# 1-12.net
KiCad netlist of a schematic drawn in EasyEDA Pro
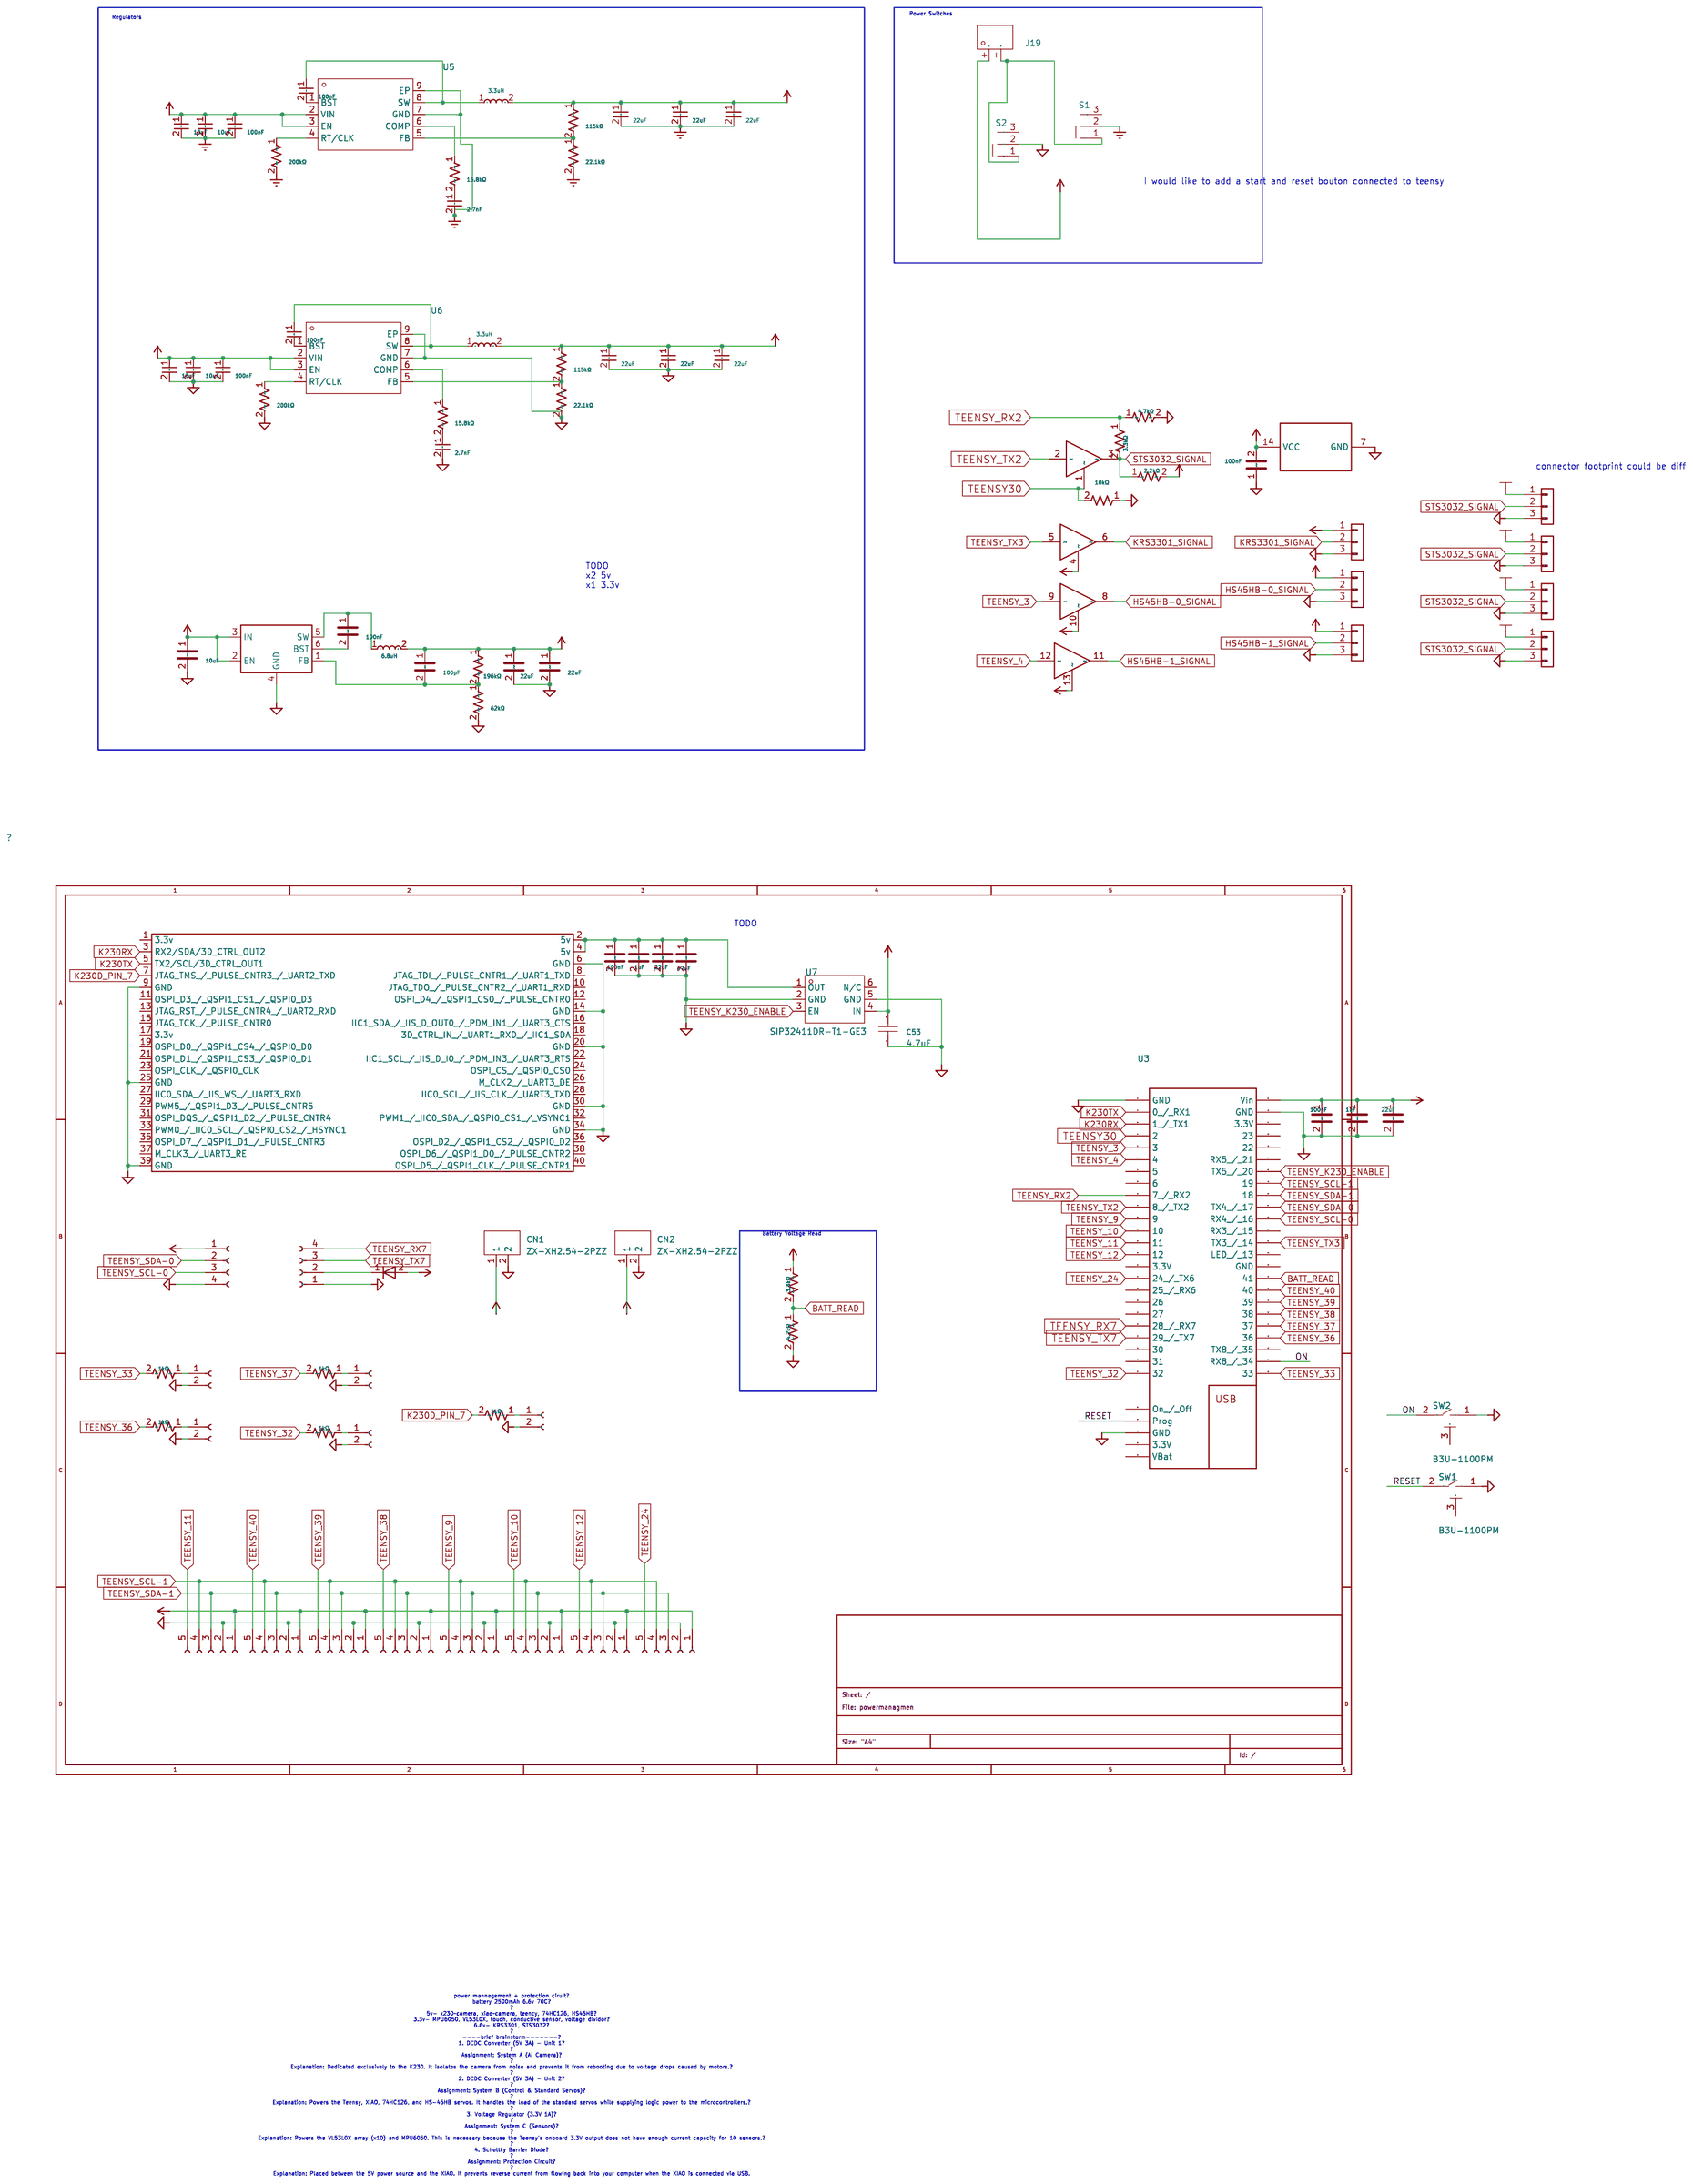
[diagram p0: schematic sheet]

(export (version "E")
  (design (tool "Eeschema 10.0.6"))
  (components
    (comp (ref "C1")
      (value "100nF")
      (description "Capacitance:100nF Tolerance:±10% Tolerance:±10% Voltage Rating:50V Temperature Coefficient:X7R")
      (fields
        (field (name "Manufacturer Part") "TCC0603X7R104K500CT")
        (field (name "Manufacturer") "CCTC(三环)")
      )
      (libsource (lib "easyedapro") (part "Device_C"))
    )
    (comp (ref "C2")
      (value "22uF")
      (description "Capacitance:22uF Tolerance:±20% Tolerance:±20% Voltage Rating:10V Temperature Coefficient:X5R")
      (fields
        (field (name "Manufacturer Part") "CL10A226MP8NUNE")
        (field (name "Manufacturer") "SAMSUNG(三星)")
      )
      (libsource (lib "easyedapro") (part "Device_C"))
    )
    (comp (ref "C3")
      (value "1uF")
      (description "Capacitance:1uF Tolerance:±10% Tolerance:±10% Voltage Rating:50V Temperature Coefficient:X5R")
      (fields
        (field (name "Manufacturer Part") "CL10A105KB8NNNC")
        (field (name "Manufacturer") "SAMSUNG(三星)")
      )
      (libsource (lib "easyedapro") (part "Device_C"))
    )
    (comp (ref "C4")
      (value "100nF")
      (description "Capacitance:100nF Tolerance:±10% Tolerance:±10% Voltage Rating:50V Temperature Coefficient:X7R")
      (fields
        (field (name "Manufacturer Part") "TCC0603X7R104K500CT")
        (field (name "Manufacturer") "CCTC(三环)")
      )
      (libsource (lib "easyedapro") (part "Device_C"))
    )
    (comp (ref "C5")
      (value "10uF")
      (description "Capacitance:10uF Tolerance:±20% Tolerance:±20% Voltage Rating:16V Temperature Coefficient:X5R")
      (fields
        (field (name "Manufacturer Part") "CL10A106MO8NQNC")
        (field (name "Manufacturer") "SAMSUNG(三星)")
      )
      (libsource (lib "easyedapro") (part "Device_C_Small"))
    )
    (comp (ref "C10")
      (value "100pF")
      (description "Capacitance:100pF Tolerance:±5% Tolerance:±5% Voltage Rating:50V Temperature Coefficient:C0G")
      (fields
        (field (name "Manufacturer Part") "CL10C101JB8NNNC")
        (field (name "Manufacturer") "SAMSUNG(三星)")
      )
      (libsource (lib "easyedapro") (part "Device_C"))
    )
    (comp (ref "C17")
      (value "100nF")
      (description "Capacitance:100nF Tolerance:±10% Tolerance:±10% Voltage Rating:50V Temperature Coefficient:X7R")
      (fields
        (field (name "Manufacturer Part") "TCC0603X7R104K500CT")
        (field (name "Manufacturer") "CCTC(三环)")
      )
      (libsource (lib "easyedapro") (part "Device_C"))
    )
    (comp (ref "C18")
      (value "1uF")
      (description "Capacitance:1uF Tolerance:±10% Tolerance:±10% Voltage Rating:50V Temperature Coefficient:X5R")
      (fields
        (field (name "Manufacturer Part") "CL10A105KB8NNNC")
        (field (name "Manufacturer") "SAMSUNG(三星)")
      )
      (libsource (lib "easyedapro") (part "Device_C"))
    )
    (comp (ref "C19")
      (value "22uF")
      (description "Capacitance:22uF Tolerance:±20% Tolerance:±20% Voltage Rating:10V Temperature Coefficient:X5R")
      (fields
        (field (name "Manufacturer Part") "CL10A226MP8NUNE")
        (field (name "Manufacturer") "SAMSUNG(三星)")
      )
      (libsource (lib "easyedapro") (part "Device_C"))
    )
    (comp (ref "C20")
      (value "47uF")
      (description "Capacitance:47uF Tolerance:±20% Tolerance:±20% Voltage Rating:6.3V Temperature Coefficient:X5R")
      (fields
        (field (name "Manufacturer Part") "GRM188R60J476ME15D")
        (field (name "Manufacturer") "muRata(村田)")
      )
      (libsource (lib "easyedapro") (part "Device_C"))
    )
    (comp (ref "C21")
      (value "22uF")
      (description "Capacitance:22uF Tolerance:±20% Tolerance:±20% Voltage Rating:10V Temperature Coefficient:X5R")
      (fields
        (field (name "Manufacturer Part") "CL10A226MP8NUNE")
        (field (name "Manufacturer") "SAMSUNG(三星)")
      )
      (libsource (lib "easyedapro") (part "Device_C"))
    )
    (comp (ref "C22")
      (value "10uF")
      (description "Capacitance:10uF Tolerance:±20% Tolerance:±20% Voltage Rating:16V Temperature Coefficient:X5R")
      (fields
        (field (name "Manufacturer Part") "CL10A106MO8NQNC")
        (field (name "Manufacturer") "SAMSUNG(三星)")
      )
      (libsource (lib "easyedapro") (part "Device_C_Small"))
    )
    (comp (ref "C23")
      (value "100nF")
      (description "Capacitance:100nF Tolerance:±10% Tolerance:±10% Voltage Rating:50V Temperature Coefficient:X7R")
      (fields
        (field (name "Manufacturer Part") "TCC0603X7R104K500CT")
        (field (name "Manufacturer") "CCTC(三环)")
      )
      (libsource (lib "easyedapro") (part "Device_C"))
    )
    (comp (ref "C24")
      (value "100nF")
      (description "Capacitance:100nF Tolerance:±10% Tolerance:±10% Voltage Rating:50V Temperature Coefficient:X7R")
      (fields
        (field (name "Manufacturer Part") "TCC0603X7R104K500CT")
        (field (name "Manufacturer") "CCTC(三环)")
      )
      (libsource (lib "easyedapro") (part "Device_C_Small"))
    )
    (comp (ref "C29")
      (value "22uF")
      (description "Capacitance:22uF Tolerance:±20% Tolerance:±20% Voltage Rating:10V Temperature Coefficient:X5R")
      (fields
        (field (name "Manufacturer Part") "CL10A226MP8NUNE")
        (field (name "Manufacturer") "SAMSUNG(三星)")
      )
      (libsource (lib "easyedapro") (part "Device_C"))
    )
    (comp (ref "C31")
      (value "10uF")
      (description "Capacitance:10uF Tolerance:±20% Tolerance:±20% Voltage Rating:16V Temperature Coefficient:X5R")
      (fields
        (field (name "Manufacturer Part") "CL10A106MO8NQNC")
        (field (name "Manufacturer") "SAMSUNG(三星)")
      )
      (libsource (lib "easyedapro") (part "Device_C"))
    )
    (comp (ref "C40")
      (value "100nF")
      (description "Capacitance:100nF Tolerance:±10% Tolerance:±10% Voltage Rating:50V Temperature Coefficient:X7R")
      (fields
        (field (name "Manufacturer Part") "TCC0603X7R104K500CT")
        (field (name "Manufacturer") "CCTC(三环)")
      )
      (libsource (lib "easyedapro") (part "Device_C_Small"))
    )
    (comp (ref "C41")
      (value "22uF")
      (description "Capacitance:22uF Tolerance:±20% Tolerance:±20% Voltage Rating:10V Temperature Coefficient:X5R")
      (fields
        (field (name "Manufacturer Part") "CL10A226MP8NUNE")
        (field (name "Manufacturer") "SAMSUNG(三星)")
      )
      (libsource (lib "easyedapro") (part "Device_C_Small"))
    )
    (comp (ref "C42")
      (value "22uF")
      (description "Capacitance:22uF Tolerance:±20% Tolerance:±20% Voltage Rating:10V Temperature Coefficient:X5R")
      (fields
        (field (name "Manufacturer Part") "CL10A226MP8NUNE")
        (field (name "Manufacturer") "SAMSUNG(三星)")
      )
      (libsource (lib "easyedapro") (part "Device_C_Small"))
    )
    (comp (ref "C43")
      (value "22uF")
      (description "Capacitance:22uF Tolerance:±20% Tolerance:±20% Voltage Rating:10V Temperature Coefficient:X5R")
      (fields
        (field (name "Manufacturer Part") "CL10A226MP8NUNE")
        (field (name "Manufacturer") "SAMSUNG(三星)")
      )
      (libsource (lib "easyedapro") (part "Device_C_Small"))
    )
    (comp (ref "C44")
      (value "2.7nF")
      (description "Capacitance:2.7nF Tolerance:±5% Tolerance:±5% Voltage Rating:50V Temperature Coefficient:C0G")
      (fields
        (field (name "Manufacturer Part") "GRM1885C1H272JA01D")
        (field (name "Manufacturer") "muRata(村田)")
      )
      (libsource (lib "easyedapro") (part "Device_C_Small"))
    )
    (comp (ref "C45")
      (value "10uF")
      (description "Capacitance:10uF Tolerance:±20% Tolerance:±20% Voltage Rating:16V Temperature Coefficient:X5R")
      (fields
        (field (name "Manufacturer Part") "CL10A106MO8NQNC")
        (field (name "Manufacturer") "SAMSUNG(三星)")
      )
      (libsource (lib "easyedapro") (part "Device_C_Small"))
    )
    (comp (ref "C46")
      (value "10uF")
      (description "Capacitance:10uF Tolerance:±20% Tolerance:±20% Voltage Rating:16V Temperature Coefficient:X5R")
      (fields
        (field (name "Manufacturer Part") "CL10A106MO8NQNC")
        (field (name "Manufacturer") "SAMSUNG(三星)")
      )
      (libsource (lib "easyedapro") (part "Device_C_Small"))
    )
    (comp (ref "C47")
      (value "100nF")
      (description "Capacitance:100nF Tolerance:±10% Tolerance:±10% Voltage Rating:50V Temperature Coefficient:X7R")
      (fields
        (field (name "Manufacturer Part") "TCC0603X7R104K500CT")
        (field (name "Manufacturer") "CCTC(三环)")
      )
      (libsource (lib "easyedapro") (part "Device_C_Small"))
    )
    (comp (ref "C48")
      (value "100nF")
      (description "Capacitance:100nF Tolerance:±10% Tolerance:±10% Voltage Rating:50V Temperature Coefficient:X7R")
      (fields
        (field (name "Manufacturer Part") "TCC0603X7R104K500CT")
        (field (name "Manufacturer") "CCTC(三环)")
      )
      (libsource (lib "easyedapro") (part "Device_C_Small"))
    )
    (comp (ref "C49")
      (value "22uF")
      (description "Capacitance:22uF Tolerance:±20% Tolerance:±20% Voltage Rating:10V Temperature Coefficient:X5R")
      (fields
        (field (name "Manufacturer Part") "CL10A226MP8NUNE")
        (field (name "Manufacturer") "SAMSUNG(三星)")
      )
      (libsource (lib "easyedapro") (part "Device_C_Small"))
    )
    (comp (ref "C50")
      (value "22uF")
      (description "Capacitance:22uF Tolerance:±20% Tolerance:±20% Voltage Rating:10V Temperature Coefficient:X5R")
      (fields
        (field (name "Manufacturer Part") "CL10A226MP8NUNE")
        (field (name "Manufacturer") "SAMSUNG(三星)")
      )
      (libsource (lib "easyedapro") (part "Device_C_Small"))
    )
    (comp (ref "C51")
      (value "22uF")
      (description "Capacitance:22uF Tolerance:±20% Tolerance:±20% Voltage Rating:10V Temperature Coefficient:X5R")
      (fields
        (field (name "Manufacturer Part") "CL10A226MP8NUNE")
        (field (name "Manufacturer") "SAMSUNG(三星)")
      )
      (libsource (lib "easyedapro") (part "Device_C_Small"))
    )
    (comp (ref "C52")
      (value "2.7nF")
      (description "Capacitance:2.7nF Tolerance:±5% Tolerance:±5% Voltage Rating:50V Temperature Coefficient:C0G")
      (fields
        (field (name "Manufacturer Part") "GRM1885C1H272JA01D")
        (field (name "Manufacturer") "muRata(村田)")
      )
      (libsource (lib "easyedapro") (part "Device_C_Small"))
    )
    (comp (ref "C53")
      (value "4.7uF")
      (footprint "easyedapro:C0603")
      (description "Capacitance:4.7uF Tolerance:±10% Tolerance:±10% Voltage Rating:10V Temperature Coefficient:X5R")
      (fields
        (field (name "Manufacturer Part") "CL10A475KP8NNNC")
        (field (name "Manufacturer") "SAMSUNG(三星)")
      )
      (libsource (lib "easyedapro") (part "CL10A475KP8NNNC"))
    )
    (comp (ref "CN1")
      (value "ZX-XH2.54-2PZZ")
      (footprint "easyedapro:CONN-TH_2P-P2.50_HX25003-2A")
      (fields (field (name "Manufacturer") "Megastar(兆星)"))
      (libsource (lib "easyedapro") (part "ZX-XH2.54-2PZZ"))
    )
    (comp (ref "CN2")
      (value "ZX-XH2.54-2PZZ")
      (footprint "easyedapro:CONN-TH_2P-P2.50_HX25003-2A")
      (fields (field (name "Manufacturer") "Megastar(兆星)"))
      (libsource (lib "easyedapro") (part "ZX-XH2.54-2PZZ"))
    )
    (comp (ref "D3")
      (value "BAT60B")
      (fields (field (name "Manufacturer") "R+O(宏嘉诚)"))
      (libsource (lib "easyedapro") (part "Diode_1N4148WT"))
    )
    (comp (ref "J1")
      (value "B3B-XH-A(LF)(SN)")
      (fields (field (name "Manufacturer") "JST"))
      (libsource (lib "easyedapro") (part "Connector_Generic_Conn_01x03"))
    )
    (comp (ref "J2")
      (value "PZ254V-11-03P")
      (fields (field (name "Manufacturer") "XFCN(兴飞)"))
      (libsource (lib "easyedapro") (part "Connector_Generic_Conn_01x03"))
    )
    (comp (ref "J3")
      (value "PZ254V-11-03P")
      (fields (field (name "Manufacturer") "XFCN(兴飞)"))
      (libsource (lib "easyedapro") (part "Connector_Generic_Conn_01x03"))
    )
    (comp (ref "J4")
      (value "PZ254V-11-03P")
      (fields (field (name "Manufacturer") "XFCN(兴飞)"))
      (libsource (lib "easyedapro") (part "Connector_Generic_Conn_01x03"))
    )
    (comp (ref "J5")
      (value "B4B-PH-K-S(LF)(SN)")
      (fields (field (name "Manufacturer") "JST"))
      (libsource (lib "easyedapro") (part "Connector_Conn_01x04_Socket"))
    )
    (comp (ref "J6")
      (value "B2B-XH-A(LF)(SN)")
      (fields (field (name "Manufacturer") "JST"))
      (libsource (lib "easyedapro") (part "Connector_Conn_01x02_Socket"))
    )
    (comp (ref "J7")
      (value "B2B-XH-A(LF)(SN)")
      (fields (field (name "Manufacturer") "JST"))
      (libsource (lib "easyedapro") (part "Connector_Conn_01x02_Socket"))
    )
    (comp (ref "J8")
      (value "B2B-XH-A(LF)(SN)")
      (fields (field (name "Manufacturer") "JST"))
      (libsource (lib "easyedapro") (part "Connector_Conn_01x02_Socket"))
    )
    (comp (ref "J9")
      (value "B2B-XH-A(LF)(SN)")
      (fields (field (name "Manufacturer") "JST"))
      (libsource (lib "easyedapro") (part "Connector_Conn_01x02_Socket"))
    )
    (comp (ref "J10")
      (value "B2B-XH-A(LF)(SN)")
      (fields (field (name "Manufacturer") "JST"))
      (libsource (lib "easyedapro") (part "Connector_Conn_01x02_Socket"))
    )
    (comp (ref "J12")
      (value "B3B-XH-A(LF)(SN)")
      (fields (field (name "Manufacturer") "JST"))
      (libsource (lib "easyedapro") (part "Connector_Generic_Conn_01x03"))
    )
    (comp (ref "J13")
      (value "B3B-XH-A(LF)(SN)")
      (fields (field (name "Manufacturer") "JST"))
      (libsource (lib "easyedapro") (part "Connector_Generic_Conn_01x03"))
    )
    (comp (ref "J14")
      (value "B3B-XH-A(LF)(SN)")
      (fields (field (name "Manufacturer") "JST"))
      (libsource (lib "easyedapro") (part "Connector_Generic_Conn_01x03"))
    )
    (comp (ref "J18")
      (value "B5B-PH-K-S(LF)(SN)")
      (fields (field (name "Manufacturer") "JST"))
      (libsource (lib "easyedapro") (part "Connector_Conn_01x05_Socket"))
    )
    (comp (ref "J19")
      (value "XT60-F")
      (footprint "easyedapro:CONN-TH_XT60PB-F")
      (fields (field (name "Manufacturer") "AMASS(艾迈斯)"))
      (libsource (lib "easyedapro") (part "XT60-F"))
    )
    (comp (ref "J25")
      (value "B5B-PH-K-S(LF)(SN)")
      (fields (field (name "Manufacturer") "JST"))
      (libsource (lib "easyedapro") (part "Connector_Conn_01x05_Socket"))
    )
    (comp (ref "J26")
      (value "B5B-PH-K-S(LF)(SN)")
      (fields (field (name "Manufacturer") "JST"))
      (libsource (lib "easyedapro") (part "Connector_Conn_01x05_Socket"))
    )
    (comp (ref "J27")
      (value "B5B-PH-K-S(LF)(SN)")
      (fields (field (name "Manufacturer") "JST"))
      (libsource (lib "easyedapro") (part "Connector_Conn_01x05_Socket"))
    )
    (comp (ref "J28")
      (value "B5B-PH-K-S(LF)(SN)")
      (fields (field (name "Manufacturer") "JST"))
      (libsource (lib "easyedapro") (part "Connector_Conn_01x05_Socket"))
    )
    (comp (ref "J29")
      (value "B5B-PH-K-S(LF)(SN)")
      (fields (field (name "Manufacturer") "JST"))
      (libsource (lib "easyedapro") (part "Connector_Conn_01x05_Socket"))
    )
    (comp (ref "J32")
      (value "B5B-PH-K-S(LF)(SN)")
      (fields (field (name "Manufacturer") "JST"))
      (libsource (lib "easyedapro") (part "Connector_Conn_01x05_Socket"))
    )
    (comp (ref "J33")
      (value "B5B-PH-K-S(LF)(SN)")
      (fields (field (name "Manufacturer") "JST"))
      (libsource (lib "easyedapro") (part "Connector_Conn_01x05_Socket"))
    )
    (comp (ref "L3")
      (value "6.8uH")
      (fields
        (field (name "Manufacturer Part") "MGFL2012F6R8MT-LF")
        (field (name "Manufacturer") "microgate(麦捷科技)")
      )
      (libsource (lib "easyedapro") (part "Device_L"))
    )
    (comp (ref "L5")
      (value "3.3uH")
      (description "Inductance: Tolerance:±20% Tolerance:±20% Current Rating: DC Resistance(DCR):19.9mΩ")
      (fields (field (name "Manufacturer Part") "CYA0650-3.3UH") (field (name "Manufacturer") "SHOU HAN(首韩)"))
      (libsource (lib "easyedapro") (part "Device_L"))
    )
    (comp (ref "L6")
      (value "3.3uH")
      (description "Inductance: Tolerance:±20% Tolerance:±20% Current Rating: DC Resistance(DCR):19.9mΩ")
      (fields (field (name "Manufacturer Part") "CYA0650-3.3UH") (field (name "Manufacturer") "SHOU HAN(首韩)"))
      (libsource (lib "easyedapro") (part "Device_L"))
    )
    (comp (ref "R1")
      (value "10kΩ")
      (fields
        (field (name "Manufacturer Part") "0603WAF1002T5E")
        (field (name "Manufacturer") "UNI-ROYAL(厚声)")
      )
      (libsource (lib "easyedapro") (part "Device_R_US"))
    )
    (comp (ref "R4")
      (value "1kΩ")
      (fields
        (field (name "Manufacturer Part") "0603WAF4700T5E")
        (field (name "Manufacturer") "UNI-ROYAL(厚声)")
      )
      (libsource (lib "easyedapro") (part "Device_R_US"))
    )
    (comp (ref "R5")
      (value "1kΩ")
      (fields
        (field (name "Manufacturer Part") "0603WAF4700T5E")
        (field (name "Manufacturer") "UNI-ROYAL(厚声)")
      )
      (libsource (lib "easyedapro") (part "Device_R_US"))
    )
    (comp (ref "R6")
      (value "1kΩ")
      (fields
        (field (name "Manufacturer Part") "0603WAF4700T5E")
        (field (name "Manufacturer") "UNI-ROYAL(厚声)")
      )
      (libsource (lib "easyedapro") (part "Device_R_US"))
    )
    (comp (ref "R7")
      (value "1kΩ")
      (fields
        (field (name "Manufacturer Part") "0603WAF4700T5E")
        (field (name "Manufacturer") "UNI-ROYAL(厚声)")
      )
      (libsource (lib "easyedapro") (part "Device_R_US"))
    )
    (comp (ref "R8")
      (value "1kΩ")
      (fields
        (field (name "Manufacturer Part") "0603WAF1001T5E")
        (field (name "Manufacturer") "UNI-ROYAL(厚声)")
      )
      (libsource (lib "easyedapro") (part "Device_R_US"))
    )
    (comp (ref "R9")
      (value "3.3kΩ")
      (fields
        (field (name "Manufacturer Part") "0603WAF2201T5E")
        (field (name "Manufacturer") "UNI-ROYAL(厚声)")
      )
      (libsource (lib "easyedapro") (part "Device_R_US"))
    )
    (comp (ref "R10")
      (value "4.7kΩ")
      (fields
        (field (name "Manufacturer Part") "0603WAF2201T5E")
        (field (name "Manufacturer") "UNI-ROYAL(厚声)")
      )
      (libsource (lib "easyedapro") (part "Device_R_US"))
    )
    (comp (ref "R12")
      (value "196kΩ")
      (fields (field (name "Manufacturer Part") "FRC0603F1963TS") (field (name "Manufacturer") "FOJAN(富捷)"))
      (libsource (lib "easyedapro") (part "Device_R_US"))
    )
    (comp (ref "R15")
      (value "62kΩ")
      (fields (field (name "Manufacturer Part") "FRC0603F6202TS") (field (name "Manufacturer") "FOJAN(富捷)"))
      (libsource (lib "easyedapro") (part "Device_R_US"))
    )
    (comp (ref "R22")
      (value "3.3kΩ")
      (fields (field (name "Manufacturer Part") "ARG03FTC8002N") (field (name "Manufacturer") "Viking(光颉)"))
      (libsource (lib "easyedapro") (part "Device_R_US"))
    )
    (comp (ref "R23")
      (value "4.7kΩ")
      (fields (field (name "Manufacturer Part") "FRC0603F2002TS") (field (name "Manufacturer") "FOJAN(富捷)"))
      (libsource (lib "easyedapro") (part "Device_R_US"))
    )
    (comp (ref "R27")
      (value "2.2kΩ")
      (fields
        (field (name "Manufacturer Part") "0603WAF2201T5E")
        (field (name "Manufacturer") "UNI-ROYAL(厚声)")
      )
      (libsource (lib "easyedapro") (part "Device_R_US"))
    )
    (comp (ref "R28")
      (value "115kΩ")
      (fields
        (field (name "Manufacturer Part") "0603WAF1153T5E")
        (field (name "Manufacturer") "UNI-ROYAL(厚声)")
      )
      (libsource (lib "easyedapro") (part "Device_R_US"))
    )
    (comp (ref "R29")
      (value "22.1kΩ")
      (fields
        (field (name "Manufacturer Part") "0603WAF2212T5E")
        (field (name "Manufacturer") "UNI-ROYAL(厚声)")
      )
      (libsource (lib "easyedapro") (part "Device_R_US"))
    )
    (comp (ref "R30")
      (value "15.8kΩ")
      (fields (field (name "Manufacturer Part") "FRC0603F1582TS") (field (name "Manufacturer") "FOJAN(富捷)"))
      (libsource (lib "easyedapro") (part "Device_R_US"))
    )
    (comp (ref "R31")
      (value "200kΩ")
      (fields
        (field (name "Manufacturer Part") "0603WAF2003T5E")
        (field (name "Manufacturer") "UNI-ROYAL(厚声)")
      )
      (libsource (lib "easyedapro") (part "Device_R_US"))
    )
    (comp (ref "R32")
      (value "200kΩ")
      (fields
        (field (name "Manufacturer Part") "0603WAF2003T5E")
        (field (name "Manufacturer") "UNI-ROYAL(厚声)")
      )
      (libsource (lib "easyedapro") (part "Device_R_US"))
    )
    (comp (ref "R33")
      (value "115kΩ")
      (fields
        (field (name "Manufacturer Part") "0603WAF1153T5E")
        (field (name "Manufacturer") "UNI-ROYAL(厚声)")
      )
      (libsource (lib "easyedapro") (part "Device_R_US"))
    )
    (comp (ref "R34")
      (value "22.1kΩ")
      (fields
        (field (name "Manufacturer Part") "0603WAF2212T5E")
        (field (name "Manufacturer") "UNI-ROYAL(厚声)")
      )
      (libsource (lib "easyedapro") (part "Device_R_US"))
    )
    (comp (ref "R35")
      (value "15.8kΩ")
      (fields (field (name "Manufacturer Part") "FRC0603F1582TS") (field (name "Manufacturer") "FOJAN(富捷)"))
      (libsource (lib "easyedapro") (part "Device_R_US"))
    )
    (comp (ref "S1")
      (value "SS-12M11G4")
      (footprint "easyedapro:SW-TH_XKB_SS-12M11XX")
      (fields (field (name "Manufacturer") "XKB Connection(中国星坤)"))
      (libsource (lib "easyedapro") (part "SS-12M11G4"))
    )
    (comp (ref "S2")
      (value "SS-12M11G4")
      (footprint "easyedapro:SW-TH_XKB_SS-12M11XX")
      (fields (field (name "Manufacturer") "XKB Connection(中国星坤)"))
      (libsource (lib "easyedapro") (part "SS-12M11G4"))
    )
    (comp (ref "SW1")
      (value "B3U-1100PM")
      (footprint "easyedapro:SW-SMD_3P-L3.0-W2.5-LS4.0")
      (fields (field (name "Manufacturer") "OMRON(欧姆龙)"))
      (libsource (lib "easyedapro") (part "B3U-1100PM"))
    )
    (comp (ref "SW2")
      (value "B3U-1100PM")
      (footprint "easyedapro:SW-SMD_3P-L3.0-W2.5-LS4.0")
      (fields (field (name "Manufacturer") "OMRON(欧姆龙)"))
      (libsource (lib "easyedapro") (part "B3U-1100PM"))
    )
    (comp (ref "U1")
      (value "CD74HCT126M96")
      (fields (field (name "Manufacturer") "TI(德州仪器)"))
      (libsource (lib "easyedapro") (part "74xx_74LS126"))
    )
    (comp (ref "U2")
      (value "FH-00148")
      (fields (field (name "Manufacturer") "Liansheng(连盛)"))
      (libsource (lib "easyedapro") (part "K230D_K230D-Zero"))
    )
    (comp (ref "U3") (value "TEENSY 4.1") (libsource (lib "easyedapro") (part "TEENSY 4.1")))
    (comp (ref "U4")
      (value "AP63201WU-7")
      (fields (field (name "Manufacturer") "DIODES(美台)"))
      (libsource (lib "easyedapro") (part "Regulator_Switching_AP63201WU"))
    )
    (comp (ref "U5")
      (value "AP64500SP-13")
      (footprint "easyedapro:SO-8_L4.9-W3.9-P1.27-LS6.0-BL-EP")
      (fields (field (name "Manufacturer") "DIODES(美台)"))
      (libsource (lib "easyedapro") (part "AP64500SP-13"))
    )
    (comp (ref "U6")
      (value "AP64500SP-13")
      (footprint "easyedapro:SO-8_L4.9-W3.9-P1.27-LS6.0-BL-EP")
      (fields (field (name "Manufacturer") "DIODES(美台)"))
      (libsource (lib "easyedapro") (part "AP64500SP-13"))
    )
    (comp (ref "U7")
      (value "SIP32411DR-T1-GE3")
      (footprint "easyedapro:SC-70-6_L2.1-W1.3-P0.65-LS2.1-BR")
      (fields (field (name "Manufacturer") "VISHAY(威世)"))
      (libsource (lib "easyedapro") (part "SIP32411DR-T1-GE3"))
    )
    (comp (ref "XIAO")
      (value "22035045")
      (fields (field (name "Manufacturer") "MOLEX"))
      (libsource (lib "easyedapro") (part "Connector_Conn_01x04_Socket"))
    )
  )
  (nets
    (net (code "1") (name "+3.3V") (class "Default")
      (node (ref "C10") (pin "1") (pinfunction "~_1") (pintype "unspecified"))
      (node (ref "C21") (pin "1") (pinfunction "~_1") (pintype "unspecified"))
      (node (ref "C29") (pin "1") (pinfunction "~_1") (pintype "unspecified"))
      (node (ref "J18") (pin "1") (pinfunction "Pin_1_1") (pintype "unspecified"))
      (node (ref "J25") (pin "1") (pinfunction "Pin_1_1") (pintype "unspecified"))
      (node (ref "J26") (pin "1") (pinfunction "Pin_1_1") (pintype "unspecified"))
      (node (ref "J27") (pin "1") (pinfunction "Pin_1_1") (pintype "unspecified"))
      (node (ref "J28") (pin "1") (pinfunction "Pin_1_1") (pintype "unspecified"))
      (node (ref "J29") (pin "1") (pinfunction "Pin_1_1") (pintype "unspecified"))
      (node (ref "J32") (pin "1") (pinfunction "Pin_1_1") (pintype "unspecified"))
      (node (ref "J33") (pin "1") (pinfunction "Pin_1_1") (pintype "unspecified"))
      (node (ref "J5") (pin "1") (pinfunction "Pin_1_1") (pintype "unspecified"))
      (node (ref "L3") (pin "2") (pinfunction "2_2") (pintype "unspecified"))
      (node (ref "R12") (pin "1") (pinfunction "~_1") (pintype "unspecified"))
    )
    (net (code "2") (name "+5V") (class "Default")
      (node (ref "C1") (pin "2") (pinfunction "~_2") (pintype "unspecified"))
      (node (ref "C2") (pin "1") (pinfunction "~_1") (pintype "unspecified"))
      (node (ref "C3") (pin "1") (pinfunction "~_1") (pintype "unspecified"))
      (node (ref "C4") (pin "1") (pinfunction "~_1") (pintype "unspecified"))
      (node (ref "C49") (pin "1") (pinfunction "~_1") (pintype "unspecified"))
      (node (ref "C50") (pin "1") (pinfunction "~_1") (pintype "unspecified"))
      (node (ref "C51") (pin "1") (pinfunction "~_1") (pintype "unspecified"))
      (node (ref "C53") (pin "2") (pinfunction "2_2") (pintype "input"))
      (node (ref "D3") (pin "2") (pinfunction "A_2") (pintype "unspecified"))
      (node (ref "J2") (pin "1") (pinfunction "Pin_1_1") (pintype "unspecified"))
      (node (ref "J3") (pin "1") (pinfunction "Pin_1_1") (pintype "unspecified"))
      (node (ref "J4") (pin "1") (pinfunction "Pin_1_1") (pintype "unspecified"))
      (node (ref "L6") (pin "2") (pinfunction "2_2") (pintype "unspecified"))
      (node (ref "R27") (pin "2") (pinfunction "~_2") (pintype "unspecified"))
      (node (ref "R33") (pin "1") (pinfunction "~_1") (pintype "unspecified"))
      (node (ref "U1") (pin "10") (pinfunction "~_10") (pintype "input"))
      (node (ref "U1") (pin "13") (pinfunction "~_13") (pintype "input"))
      (node (ref "U1") (pin "14") (pinfunction "VCC_14") (pintype "unspecified"))
      (node (ref "U1") (pin "4") (pinfunction "~_4") (pintype "input"))
      (node (ref "U3") (pin "25") (pinfunction "Vin_25") (pintype "unspecified"))
      (node (ref "U7") (pin "4") (pinfunction "IN_4") (pintype "input"))
    )
    (net (code "3") (name "+5VM") (class "Default")
      (node (ref "C41") (pin "1") (pinfunction "~_1") (pintype "unspecified"))
      (node (ref "C42") (pin "1") (pinfunction "~_1") (pintype "unspecified"))
      (node (ref "C43") (pin "1") (pinfunction "~_1") (pintype "unspecified"))
      (node (ref "J1") (pin "1") (pinfunction "Pin_1_1") (pintype "unspecified"))
      (node (ref "J12") (pin "1") (pinfunction "Pin_1_1") (pintype "unspecified"))
      (node (ref "J13") (pin "1") (pinfunction "Pin_1_1") (pintype "unspecified"))
      (node (ref "J14") (pin "1") (pinfunction "Pin_1_1") (pintype "unspecified"))
      (node (ref "L5") (pin "2") (pinfunction "2_2") (pintype "unspecified"))
      (node (ref "R28") (pin "1") (pinfunction "~_1") (pintype "unspecified"))
    )
    (net (code "4") (name "+BATT") (class "Default")
      (node (ref "C22") (pin "1") (pinfunction "~_1") (pintype "unspecified"))
      (node (ref "C24") (pin "1") (pinfunction "~_1") (pintype "unspecified"))
      (node (ref "C31") (pin "1") (pinfunction "~_1") (pintype "unspecified"))
      (node (ref "C45") (pin "1") (pinfunction "~_1") (pintype "unspecified"))
      (node (ref "C46") (pin "1") (pinfunction "~_1") (pintype "unspecified"))
      (node (ref "C47") (pin "1") (pinfunction "~_1") (pintype "unspecified"))
      (node (ref "C5") (pin "1") (pinfunction "~_1") (pintype "unspecified"))
      (node (ref "CN1") (pin "1") (pinfunction "1_1") (pintype "unspecified"))
      (node (ref "CN2") (pin "1") (pinfunction "1_1") (pintype "unspecified"))
      (node (ref "J19") (pin "+") (pinfunction "1_+") (pintype "input"))
      (node (ref "R22") (pin "1") (pinfunction "~_1") (pintype "unspecified"))
      (node (ref "U4") (pin "2") (pinfunction "EN_2") (pintype "input"))
      (node (ref "U4") (pin "3") (pinfunction "IN_3") (pintype "unspecified"))
      (node (ref "U5") (pin "2") (pinfunction "VIN_2") (pintype "unspecified"))
      (node (ref "U5") (pin "3") (pinfunction "EN_3") (pintype "unspecified"))
      (node (ref "U6") (pin "2") (pinfunction "VIN_2") (pintype "unspecified"))
      (node (ref "U6") (pin "3") (pinfunction "EN_3") (pintype "unspecified"))
    )
    (net (code "5") (name "/ON") (class "Default")
      (node (ref "SW2") (pin "2") (pinfunction "2_2") (pintype "unspecified"))
      (node (ref "U3") (pin "47") (pinfunction "RX8_/_34_47") (pintype "unspecified"))
    )
    (net (code "6") (name "/RESET") (class "Default")
      (node (ref "SW1") (pin "2") (pinfunction "2_2") (pintype "unspecified"))
      (node (ref "U3") (pin "50") (pinfunction "Prog_50") (pintype "unspecified"))
    )
    (net (code "7") (name "BATT_READ") (class "Default")
      (node (ref "R22") (pin "2") (pinfunction "~_2") (pintype "unspecified"))
      (node (ref "R23") (pin "1") (pinfunction "~_1") (pintype "unspecified"))
      (node (ref "U3") (pin "40") (pinfunction "41_40") (pintype "unspecified"))
    )
    (net (code "8") (name "HS45HB-0_SIGNAL") (class "Default")
      (node (ref "J3") (pin "2") (pinfunction "Pin_2_2") (pintype "unspecified"))
      (node (ref "U1") (pin "8") (pinfunction "~_8") (pintype "unspecified"))
    )
    (net (code "9") (name "HS45HB-1_SIGNAL") (class "Default")
      (node (ref "J4") (pin "2") (pinfunction "Pin_2_2") (pintype "unspecified"))
      (node (ref "U1") (pin "11") (pinfunction "~_11") (pintype "unspecified"))
    )
    (net (code "10") (name "K230D_PIN_7") (class "Default")
      (node (ref "R8") (pin "2") (pinfunction "~_2") (pintype "unspecified"))
      (node (ref "U2") (pin "7") (pinfunction "JTAG_TMS_/_PULSE_CNTR3_/_UART2_TXD_7") (pintype "output"))
    )
    (net (code "11") (name "K230RX") (class "Default")
      (node (ref "U2") (pin "3") (pinfunction "RX2/SDA/3D_CTRL_OUT2_3") (pintype "input"))
      (node (ref "U3") (pin "3") (pinfunction "1_/_TX1_3") (pintype "unspecified"))
    )
    (net (code "12") (name "K230TX") (class "Default")
      (node (ref "U2") (pin "5") (pinfunction "TX2/SCL/3D_CTRL_OUT1_5") (pintype "bidirectional"))
      (node (ref "U3") (pin "2") (pinfunction "0_/_RX1_2") (pintype "unspecified"))
    )
    (net (code "13") (name "KRS3301_SIGNAL") (class "Default")
      (node (ref "J2") (pin "2") (pinfunction "Pin_2_2") (pintype "unspecified"))
      (node (ref "U1") (pin "6") (pinfunction "~_6") (pintype "unspecified"))
    )
    (net (code "14") (name "MGND") (class "Default")
      (node (ref "C22") (pin "2") (pinfunction "~_2") (pintype "unspecified"))
      (node (ref "C24") (pin "2") (pinfunction "~_2") (pintype "unspecified"))
      (node (ref "C41") (pin "2") (pinfunction "~_2") (pintype "unspecified"))
      (node (ref "C42") (pin "2") (pinfunction "~_2") (pintype "unspecified"))
      (node (ref "C43") (pin "2") (pinfunction "~_2") (pintype "unspecified"))
      (node (ref "C44") (pin "2") (pinfunction "~_2") (pintype "unspecified"))
      (node (ref "C5") (pin "2") (pinfunction "~_2") (pintype "unspecified"))
      (node (ref "R29") (pin "2") (pinfunction "~_2") (pintype "unspecified"))
      (node (ref "R31") (pin "2") (pinfunction "~_2") (pintype "unspecified"))
      (node (ref "S1") (pin "2") (pinfunction "2_2") (pintype "unspecified"))
      (node (ref "U5") (pin "7") (pinfunction "GND_7") (pintype "unspecified"))
      (node (ref "U5") (pin "9") (pinfunction "EP_9") (pintype "unspecified"))
    )
    (net (code "15") (name "Net-(C44-~-Pad1)") (class "Default")
      (node (ref "C44") (pin "1") (pinfunction "~_1") (pintype "unspecified"))
      (node (ref "R30") (pin "2") (pinfunction "~_2") (pintype "unspecified"))
    )
    (net (code "16") (name "Net-(C52-~-Pad1)") (class "Default")
      (node (ref "C52") (pin "1") (pinfunction "~_1") (pintype "unspecified"))
      (node (ref "R35") (pin "2") (pinfunction "~_2") (pintype "unspecified"))
    )
    (net (code "17") (name "Net-(D3-K)") (class "Default")
      (node (ref "D3") (pin "1") (pinfunction "K_1") (pintype "unspecified"))
      (node (ref "XIAO") (pin "2") (pinfunction "Pin_2_2") (pintype "unspecified"))
    )
    (net (code "18") (name "Net-(J6-Pin_1)") (class "Default")
      (node (ref "J6") (pin "1") (pinfunction "Pin_1_1") (pintype "unspecified"))
      (node (ref "R4") (pin "1") (pinfunction "~_1") (pintype "unspecified"))
    )
    (net (code "19") (name "Net-(J7-Pin_1)") (class "Default")
      (node (ref "J7") (pin "1") (pinfunction "Pin_1_1") (pintype "unspecified"))
      (node (ref "R5") (pin "1") (pinfunction "~_1") (pintype "unspecified"))
    )
    (net (code "20") (name "Net-(J8-Pin_1)") (class "Default")
      (node (ref "J8") (pin "1") (pinfunction "Pin_1_1") (pintype "unspecified"))
      (node (ref "R6") (pin "1") (pinfunction "~_1") (pintype "unspecified"))
    )
    (net (code "21") (name "Net-(J9-Pin_1)") (class "Default")
      (node (ref "J9") (pin "1") (pinfunction "Pin_1_1") (pintype "unspecified"))
      (node (ref "R7") (pin "1") (pinfunction "~_1") (pintype "unspecified"))
    )
    (net (code "22") (name "Net-(J10-Pin_1)") (class "Default")
      (node (ref "J10") (pin "1") (pinfunction "Pin_1_1") (pintype "unspecified"))
      (node (ref "R8") (pin "1") (pinfunction "~_1") (pintype "unspecified"))
    )
    (net (code "23") (name "Net-(J19-2)") (class "Default")
      (node (ref "J19") (pin "-") (pinfunction "2_-") (pintype "input"))
      (node (ref "S1") (pin "1") (pinfunction "1_1") (pintype "unspecified"))
      (node (ref "S2") (pin "1") (pinfunction "1_1") (pintype "unspecified"))
    )
    (net (code "24") (name "Net-(U4-BST)") (class "Default")
      (node (ref "C23") (pin "2") (pinfunction "~_2") (pintype "unspecified"))
      (node (ref "U4") (pin "6") (pinfunction "BST_6") (pintype "unspecified"))
    )
    (net (code "25") (name "Net-(U4-FB)") (class "Default")
      (node (ref "C10") (pin "2") (pinfunction "~_2") (pintype "unspecified"))
      (node (ref "R12") (pin "2") (pinfunction "~_2") (pintype "unspecified"))
      (node (ref "R15") (pin "1") (pinfunction "~_1") (pintype "unspecified"))
      (node (ref "U4") (pin "1") (pinfunction "FB_1") (pintype "input"))
    )
    (net (code "26") (name "Net-(U4-SW)") (class "Default")
      (node (ref "C23") (pin "1") (pinfunction "~_1") (pintype "unspecified"))
      (node (ref "L3") (pin "1") (pinfunction "1_1") (pintype "unspecified"))
      (node (ref "U4") (pin "5") (pinfunction "SW_5") (pintype "output"))
    )
    (net (code "27") (name "Net-(U5-BST)") (class "Default")
      (node (ref "C40") (pin "2") (pinfunction "~_2") (pintype "unspecified"))
      (node (ref "U5") (pin "1") (pinfunction "BST_1") (pintype "unspecified"))
    )
    (net (code "28") (name "Net-(U5-COMP)") (class "Default")
      (node (ref "R30") (pin "1") (pinfunction "~_1") (pintype "unspecified"))
      (node (ref "U5") (pin "6") (pinfunction "COMP_6") (pintype "unspecified"))
    )
    (net (code "29") (name "Net-(U5-FB)") (class "Default")
      (node (ref "R28") (pin "2") (pinfunction "~_2") (pintype "unspecified"))
      (node (ref "R29") (pin "1") (pinfunction "~_1") (pintype "unspecified"))
      (node (ref "U5") (pin "5") (pinfunction "FB_5") (pintype "unspecified"))
    )
    (net (code "30") (name "Net-(U5-RT{slash}CLK)") (class "Default")
      (node (ref "R31") (pin "1") (pinfunction "~_1") (pintype "unspecified"))
      (node (ref "U5") (pin "4") (pinfunction "RT/CLK_4") (pintype "unspecified"))
    )
    (net (code "31") (name "Net-(U5-SW)") (class "Default")
      (node (ref "C40") (pin "1") (pinfunction "~_1") (pintype "unspecified"))
      (node (ref "L5") (pin "1") (pinfunction "1_1") (pintype "unspecified"))
      (node (ref "U5") (pin "8") (pinfunction "SW_8") (pintype "unspecified"))
    )
    (net (code "32") (name "Net-(U6-BST)") (class "Default")
      (node (ref "C48") (pin "2") (pinfunction "~_2") (pintype "unspecified"))
      (node (ref "U6") (pin "1") (pinfunction "BST_1") (pintype "unspecified"))
    )
    (net (code "33") (name "Net-(U6-COMP)") (class "Default")
      (node (ref "R35") (pin "1") (pinfunction "~_1") (pintype "unspecified"))
      (node (ref "U6") (pin "6") (pinfunction "COMP_6") (pintype "unspecified"))
    )
    (net (code "34") (name "Net-(U6-FB)") (class "Default")
      (node (ref "R33") (pin "2") (pinfunction "~_2") (pintype "unspecified"))
      (node (ref "R34") (pin "1") (pinfunction "~_1") (pintype "unspecified"))
      (node (ref "U6") (pin "5") (pinfunction "FB_5") (pintype "unspecified"))
    )
    (net (code "35") (name "Net-(U6-RT{slash}CLK)") (class "Default")
      (node (ref "R32") (pin "1") (pinfunction "~_1") (pintype "unspecified"))
      (node (ref "U6") (pin "4") (pinfunction "RT/CLK_4") (pintype "unspecified"))
    )
    (net (code "36") (name "Net-(U6-SW)") (class "Default")
      (node (ref "C48") (pin "1") (pinfunction "~_1") (pintype "unspecified"))
      (node (ref "L6") (pin "1") (pinfunction "1_1") (pintype "unspecified"))
      (node (ref "U6") (pin "8") (pinfunction "SW_8") (pintype "unspecified"))
    )
    (net (code "37") (name "Net-(U7-OUT)") (class "Default")
      (node (ref "C17") (pin "1") (pinfunction "~_1") (pintype "unspecified"))
      (node (ref "C18") (pin "1") (pinfunction "~_1") (pintype "unspecified"))
      (node (ref "C19") (pin "1") (pinfunction "~_1") (pintype "unspecified"))
      (node (ref "C20") (pin "1") (pinfunction "~_1") (pintype "unspecified"))
      (node (ref "U2") (pin "2") (pinfunction "5v_2") (pintype "unspecified"))
      (node (ref "U2") (pin "4") (pinfunction "5v_4") (pintype "bidirectional"))
      (node (ref "U7") (pin "1") (pinfunction "OUT_1") (pintype "input"))
    )
    (net (code "38") (name "POWER_GND") (class "Default")
      (node (ref "C1") (pin "1") (pinfunction "~_1") (pintype "unspecified"))
      (node (ref "C17") (pin "2") (pinfunction "~_2") (pintype "unspecified"))
      (node (ref "C18") (pin "2") (pinfunction "~_2") (pintype "unspecified"))
      (node (ref "C19") (pin "2") (pinfunction "~_2") (pintype "unspecified"))
      (node (ref "C2") (pin "2") (pinfunction "~_2") (pintype "unspecified"))
      (node (ref "C20") (pin "2") (pinfunction "~_2") (pintype "unspecified"))
      (node (ref "C21") (pin "2") (pinfunction "~_2") (pintype "unspecified"))
      (node (ref "C29") (pin "2") (pinfunction "~_2") (pintype "unspecified"))
      (node (ref "C3") (pin "2") (pinfunction "~_2") (pintype "unspecified"))
      (node (ref "C31") (pin "2") (pinfunction "~_2") (pintype "unspecified"))
      (node (ref "C4") (pin "2") (pinfunction "~_2") (pintype "unspecified"))
      (node (ref "C45") (pin "2") (pinfunction "~_2") (pintype "unspecified"))
      (node (ref "C46") (pin "2") (pinfunction "~_2") (pintype "unspecified"))
      (node (ref "C47") (pin "2") (pinfunction "~_2") (pintype "unspecified"))
      (node (ref "C49") (pin "2") (pinfunction "~_2") (pintype "unspecified"))
      (node (ref "C50") (pin "2") (pinfunction "~_2") (pintype "unspecified"))
      (node (ref "C51") (pin "2") (pinfunction "~_2") (pintype "unspecified"))
      (node (ref "C52") (pin "2") (pinfunction "~_2") (pintype "unspecified"))
      (node (ref "C53") (pin "1") (pinfunction "1_1") (pintype "input"))
      (node (ref "CN1") (pin "2") (pinfunction "2_2") (pintype "unspecified"))
      (node (ref "CN2") (pin "2") (pinfunction "2_2") (pintype "unspecified"))
      (node (ref "J1") (pin "3") (pinfunction "Pin_3_3") (pintype "unspecified"))
      (node (ref "J10") (pin "2") (pinfunction "Pin_2_2") (pintype "unspecified"))
      (node (ref "J12") (pin "3") (pinfunction "Pin_3_3") (pintype "unspecified"))
      (node (ref "J13") (pin "3") (pinfunction "Pin_3_3") (pintype "unspecified"))
      (node (ref "J14") (pin "3") (pinfunction "Pin_3_3") (pintype "unspecified"))
      (node (ref "J18") (pin "2") (pinfunction "Pin_2_2") (pintype "unspecified"))
      (node (ref "J2") (pin "3") (pinfunction "Pin_3_3") (pintype "unspecified"))
      (node (ref "J25") (pin "2") (pinfunction "Pin_2_2") (pintype "unspecified"))
      (node (ref "J26") (pin "2") (pinfunction "Pin_2_2") (pintype "unspecified"))
      (node (ref "J27") (pin "2") (pinfunction "Pin_2_2") (pintype "unspecified"))
      (node (ref "J28") (pin "2") (pinfunction "Pin_2_2") (pintype "unspecified"))
      (node (ref "J29") (pin "2") (pinfunction "Pin_2_2") (pintype "unspecified"))
      (node (ref "J3") (pin "3") (pinfunction "Pin_3_3") (pintype "unspecified"))
      (node (ref "J32") (pin "2") (pinfunction "Pin_2_2") (pintype "unspecified"))
      (node (ref "J33") (pin "2") (pinfunction "Pin_2_2") (pintype "unspecified"))
      (node (ref "J4") (pin "3") (pinfunction "Pin_3_3") (pintype "unspecified"))
      (node (ref "J5") (pin "4") (pinfunction "Pin_4_4") (pintype "unspecified"))
      (node (ref "J6") (pin "2") (pinfunction "Pin_2_2") (pintype "unspecified"))
      (node (ref "J7") (pin "2") (pinfunction "Pin_2_2") (pintype "unspecified"))
      (node (ref "J8") (pin "2") (pinfunction "Pin_2_2") (pintype "unspecified"))
      (node (ref "J9") (pin "2") (pinfunction "Pin_2_2") (pintype "unspecified"))
      (node (ref "R1") (pin "1") (pinfunction "~_1") (pintype "unspecified"))
      (node (ref "R10") (pin "2") (pinfunction "~_2") (pintype "unspecified"))
      (node (ref "R15") (pin "2") (pinfunction "~_2") (pintype "unspecified"))
      (node (ref "R23") (pin "2") (pinfunction "~_2") (pintype "unspecified"))
      (node (ref "R32") (pin "2") (pinfunction "~_2") (pintype "unspecified"))
      (node (ref "R34") (pin "2") (pinfunction "~_2") (pintype "unspecified"))
      (node (ref "S2") (pin "2") (pinfunction "2_2") (pintype "unspecified"))
      (node (ref "SW1") (pin "1") (pinfunction "1_1") (pintype "unspecified"))
      (node (ref "SW2") (pin "1") (pinfunction "1_1") (pintype "unspecified"))
      (node (ref "U1") (pin "7") (pinfunction "GND_7") (pintype "unspecified"))
      (node (ref "U2") (pin "14") (pinfunction "GND_14") (pintype "bidirectional"))
      (node (ref "U2") (pin "20") (pinfunction "GND_20") (pintype "bidirectional"))
      (node (ref "U2") (pin "25") (pinfunction "GND_25") (pintype "bidirectional"))
      (node (ref "U2") (pin "30") (pinfunction "GND_30") (pintype "bidirectional"))
      (node (ref "U2") (pin "34") (pinfunction "GND_34") (pintype "bidirectional"))
      (node (ref "U2") (pin "39") (pinfunction "GND_39") (pintype "bidirectional"))
      (node (ref "U2") (pin "6") (pinfunction "GND_6") (pintype "bidirectional"))
      (node (ref "U2") (pin "9") (pinfunction "GND_9") (pintype "bidirectional"))
      (node (ref "U3") (pin "1") (pinfunction "GND_1") (pintype "unspecified"))
      (node (ref "U3") (pin "26") (pinfunction "GND_26") (pintype "unspecified"))
      (node (ref "U3") (pin "51") (pinfunction "GND_51") (pintype "unspecified"))
      (node (ref "U4") (pin "4") (pinfunction "GND_4") (pintype "unspecified"))
      (node (ref "U6") (pin "7") (pinfunction "GND_7") (pintype "unspecified"))
      (node (ref "U6") (pin "9") (pinfunction "EP_9") (pintype "unspecified"))
      (node (ref "U7") (pin "2") (pinfunction "GND_2") (pintype "input"))
      (node (ref "U7") (pin "5") (pinfunction "GND_5") (pintype "input"))
      (node (ref "XIAO") (pin "1") (pinfunction "Pin_1_1") (pintype "unspecified"))
    )
    (net (code "39") (name "STS3032_SIGNAL") (class "Default")
      (node (ref "J1") (pin "2") (pinfunction "Pin_2_2") (pintype "unspecified"))
      (node (ref "J12") (pin "2") (pinfunction "Pin_2_2") (pintype "unspecified"))
      (node (ref "J13") (pin "2") (pinfunction "Pin_2_2") (pintype "unspecified"))
      (node (ref "J14") (pin "2") (pinfunction "Pin_2_2") (pintype "unspecified"))
      (node (ref "R27") (pin "1") (pinfunction "~_1") (pintype "unspecified"))
      (node (ref "R9") (pin "2") (pinfunction "~_2") (pintype "unspecified"))
      (node (ref "U1") (pin "3") (pinfunction "~_3") (pintype "unspecified"))
    )
    (net (code "40") (name "TEENSY30") (class "Default")
      (node (ref "R1") (pin "2") (pinfunction "~_2") (pintype "unspecified"))
      (node (ref "U1") (pin "1") (pinfunction "~_1") (pintype "input"))
      (node (ref "U3") (pin "4") (pinfunction "2_4") (pintype "unspecified"))
    )
    (net (code "41") (name "TEENSY_3") (class "Default")
      (node (ref "U1") (pin "9") (pinfunction "~_9") (pintype "input"))
      (node (ref "U3") (pin "5") (pinfunction "3_5") (pintype "unspecified"))
    )
    (net (code "42") (name "TEENSY_4") (class "Default")
      (node (ref "U1") (pin "12") (pinfunction "~_12") (pintype "input"))
      (node (ref "U3") (pin "6") (pinfunction "4_6") (pintype "unspecified"))
    )
    (net (code "43") (name "TEENSY_9") (class "Default")
      (node (ref "J28") (pin "5") (pinfunction "Pin_5_5") (pintype "unspecified"))
      (node (ref "U3") (pin "11") (pinfunction "9_11") (pintype "unspecified"))
    )
    (net (code "44") (name "TEENSY_10") (class "Default")
      (node (ref "J29") (pin "5") (pinfunction "Pin_5_5") (pintype "unspecified"))
      (node (ref "U3") (pin "12") (pinfunction "10_12") (pintype "unspecified"))
    )
    (net (code "45") (name "TEENSY_11") (class "Default")
      (node (ref "J25") (pin "5") (pinfunction "Pin_5_5") (pintype "unspecified"))
      (node (ref "U3") (pin "13") (pinfunction "11_13") (pintype "unspecified"))
    )
    (net (code "46") (name "TEENSY_12") (class "Default")
      (node (ref "J32") (pin "5") (pinfunction "Pin_5_5") (pintype "unspecified"))
      (node (ref "U3") (pin "14") (pinfunction "12_14") (pintype "unspecified"))
    )
    (net (code "47") (name "TEENSY_24") (class "Default")
      (node (ref "J33") (pin "5") (pinfunction "Pin_5_5") (pintype "unspecified"))
      (node (ref "U3") (pin "16") (pinfunction "24_/_TX6_16") (pintype "unspecified"))
    )
    (net (code "48") (name "TEENSY_32") (class "Default")
      (node (ref "R7") (pin "2") (pinfunction "~_2") (pintype "unspecified"))
      (node (ref "U3") (pin "24") (pinfunction "32_24") (pintype "unspecified"))
    )
    (net (code "49") (name "TEENSY_33") (class "Default")
      (node (ref "R4") (pin "2") (pinfunction "~_2") (pintype "unspecified"))
      (node (ref "U3") (pin "48") (pinfunction "33_48") (pintype "unspecified"))
    )
    (net (code "50") (name "TEENSY_36") (class "Default")
      (node (ref "R5") (pin "2") (pinfunction "~_2") (pintype "unspecified"))
      (node (ref "U3") (pin "45") (pinfunction "36_45") (pintype "unspecified"))
    )
    (net (code "51") (name "TEENSY_37") (class "Default")
      (node (ref "R6") (pin "2") (pinfunction "~_2") (pintype "unspecified"))
      (node (ref "U3") (pin "44") (pinfunction "37_44") (pintype "unspecified"))
    )
    (net (code "52") (name "TEENSY_38") (class "Default")
      (node (ref "J27") (pin "5") (pinfunction "Pin_5_5") (pintype "unspecified"))
      (node (ref "U3") (pin "43") (pinfunction "38_43") (pintype "unspecified"))
    )
    (net (code "53") (name "TEENSY_39") (class "Default")
      (node (ref "J26") (pin "5") (pinfunction "Pin_5_5") (pintype "unspecified"))
      (node (ref "U3") (pin "42") (pinfunction "39_42") (pintype "unspecified"))
    )
    (net (code "54") (name "TEENSY_40") (class "Default")
      (node (ref "J18") (pin "5") (pinfunction "Pin_5_5") (pintype "unspecified"))
      (node (ref "U3") (pin "41") (pinfunction "40_41") (pintype "unspecified"))
    )
    (net (code "55") (name "TEENSY_K230_ENABLE") (class "Default")
      (node (ref "U3") (pin "31") (pinfunction "TX5_/_20_31") (pintype "unspecified"))
      (node (ref "U7") (pin "3") (pinfunction "EN_3") (pintype "input"))
    )
    (net (code "56") (name "TEENSY_RX2") (class "Default")
      (node (ref "R10") (pin "1") (pinfunction "~_1") (pintype "unspecified"))
      (node (ref "R9") (pin "1") (pinfunction "~_1") (pintype "unspecified"))
      (node (ref "U3") (pin "9") (pinfunction "7_/_RX2_9") (pintype "unspecified"))
    )
    (net (code "57") (name "TEENSY_RX7") (class "Default")
      (node (ref "U3") (pin "20") (pinfunction "28_/_RX7_20") (pintype "unspecified"))
      (node (ref "XIAO") (pin "4") (pinfunction "Pin_4_4") (pintype "unspecified"))
    )
    (net (code "58") (name "TEENSY_SCL-0") (class "Default")
      (node (ref "J5") (pin "3") (pinfunction "Pin_3_3") (pintype "unspecified"))
      (node (ref "U3") (pin "35") (pinfunction "RX4_/_16_35") (pintype "unspecified"))
    )
    (net (code "59") (name "TEENSY_SCL-1") (class "Default")
      (node (ref "J18") (pin "4") (pinfunction "Pin_4_4") (pintype "unspecified"))
      (node (ref "J25") (pin "4") (pinfunction "Pin_4_4") (pintype "unspecified"))
      (node (ref "J26") (pin "4") (pinfunction "Pin_4_4") (pintype "unspecified"))
      (node (ref "J27") (pin "4") (pinfunction "Pin_4_4") (pintype "unspecified"))
      (node (ref "J28") (pin "4") (pinfunction "Pin_4_4") (pintype "unspecified"))
      (node (ref "J29") (pin "4") (pinfunction "Pin_4_4") (pintype "unspecified"))
      (node (ref "J32") (pin "4") (pinfunction "Pin_4_4") (pintype "unspecified"))
      (node (ref "J33") (pin "4") (pinfunction "Pin_4_4") (pintype "unspecified"))
      (node (ref "U3") (pin "32") (pinfunction "19_32") (pintype "unspecified"))
    )
    (net (code "60") (name "TEENSY_SDA-0") (class "Default")
      (node (ref "J5") (pin "2") (pinfunction "Pin_2_2") (pintype "unspecified"))
      (node (ref "U3") (pin "34") (pinfunction "TX4_/_17_34") (pintype "unspecified"))
    )
    (net (code "61") (name "TEENSY_SDA-1") (class "Default")
      (node (ref "J18") (pin "3") (pinfunction "Pin_3_3") (pintype "unspecified"))
      (node (ref "J25") (pin "3") (pinfunction "Pin_3_3") (pintype "unspecified"))
      (node (ref "J26") (pin "3") (pinfunction "Pin_3_3") (pintype "unspecified"))
      (node (ref "J27") (pin "3") (pinfunction "Pin_3_3") (pintype "unspecified"))
      (node (ref "J28") (pin "3") (pinfunction "Pin_3_3") (pintype "unspecified"))
      (node (ref "J29") (pin "3") (pinfunction "Pin_3_3") (pintype "unspecified"))
      (node (ref "J32") (pin "3") (pinfunction "Pin_3_3") (pintype "unspecified"))
      (node (ref "J33") (pin "3") (pinfunction "Pin_3_3") (pintype "unspecified"))
      (node (ref "U3") (pin "33") (pinfunction "18_33") (pintype "unspecified"))
    )
    (net (code "62") (name "TEENSY_TX2") (class "Default")
      (node (ref "U1") (pin "2") (pinfunction "~_2") (pintype "input"))
      (node (ref "U3") (pin "10") (pinfunction "8_/_TX2_10") (pintype "unspecified"))
    )
    (net (code "63") (name "TEENSY_TX3") (class "Default")
      (node (ref "U1") (pin "5") (pinfunction "~_5") (pintype "input"))
      (node (ref "U3") (pin "37") (pinfunction "TX3_/_14_37") (pintype "unspecified"))
    )
    (net (code "64") (name "TEENSY_TX7") (class "Default")
      (node (ref "U3") (pin "21") (pinfunction "29_/_TX7_21") (pintype "unspecified"))
      (node (ref "XIAO") (pin "3") (pinfunction "Pin_3_3") (pintype "unspecified"))
    )
    (net (code "65") (name "unconnected-(S1-Pad3)") (class "Default")
      (node (ref "S1") (pin "3") (pinfunction "3_3") (pintype "unspecified"))
    )
    (net (code "66") (name "unconnected-(S2-Pad3)") (class "Default")
      (node (ref "S2") (pin "3") (pinfunction "3_3") (pintype "unspecified"))
    )
    (net (code "67") (name "unconnected-(SW1-Pad3)") (class "Default")
      (node (ref "SW1") (pin "3") (pinfunction "3_3") (pintype "unspecified"))
    )
    (net (code "68") (name "unconnected-(SW2-Pad3)") (class "Default")
      (node (ref "SW2") (pin "3") (pinfunction "3_3") (pintype "unspecified"))
    )
    (net (code "69") (name "unconnected-(U2-3.3v-Pad1)") (class "Default")
      (node (ref "U2") (pin "1") (pinfunction "3.3v_1") (pintype "unspecified"))
    )
    (net (code "70") (name "unconnected-(U2-3.3v-Pad17)") (class "Default")
      (node (ref "U2") (pin "17") (pinfunction "3.3v_17") (pintype "bidirectional"))
    )
    (net (code "71") (name "unconnected-(U2-3D_CTRL_IN_{slash}_UART1_RXD_{slash}_IIC1_SDA-Pad18)") (class "Default")
      (node (ref "U2") (pin "18") (pinfunction "3D_CTRL_IN_/_UART1_RXD_/_IIC1_SDA_18") (pintype "bidirectional"))
    )
    (net (code "72") (name "unconnected-(U2-IIC0_SCL_{slash}_IIS_CLK_{slash}_UART3_TXD-Pad28)") (class "Default")
      (node (ref "U2") (pin "28") (pinfunction "IIC0_SCL_/_IIS_CLK_/_UART3_TXD_28") (pintype "bidirectional"))
    )
    (net (code "73") (name "unconnected-(U2-IIC0_SDA_{slash}_IIS_WS_{slash}_UART3_RXD-Pad27)") (class "Default")
      (node (ref "U2") (pin "27") (pinfunction "IIC0_SDA_/_IIS_WS_/_UART3_RXD_27") (pintype "bidirectional"))
    )
    (net (code "74") (name "unconnected-(U2-IIC1_SCL_{slash}_IIS_D_I0_{slash}_PDM_IN3_{slash}_UART3_RTS-Pad22)") (class "Default")
      (node (ref "U2") (pin "22") (pinfunction "IIC1_SCL_/_IIS_D_I0_/_PDM_IN3_/_UART3_RTS_22") (pintype "bidirectional"))
    )
    (net (code "75") (name "unconnected-(U2-IIC1_SDA_{slash}_IIS_D_OUT0_{slash}_PDM_IN1_{slash}_UART3_CTS-Pad16)") (class "Default")
      (node (ref "U2") (pin "16") (pinfunction "IIC1_SDA_/_IIS_D_OUT0_/_PDM_IN1_/_UART3_CTS_16") (pintype "bidirectional"))
    )
    (net (code "76") (name "unconnected-(U2-JTAG_RST_{slash}_PULSE_CNTR4_{slash}_UART2_RXD-Pad13)") (class "Default")
      (node (ref "U2") (pin "13") (pinfunction "JTAG_RST_/_PULSE_CNTR4_/_UART2_RXD_13") (pintype "bidirectional"))
    )
    (net (code "77") (name "unconnected-(U2-JTAG_TCK_{slash}_PULSE_CNTR0-Pad15)") (class "Default")
      (node (ref "U2") (pin "15") (pinfunction "JTAG_TCK_/_PULSE_CNTR0_15") (pintype "bidirectional"))
    )
    (net (code "78") (name "unconnected-(U2-JTAG_TDI_{slash}_PULSE_CNTR1_{slash}_UART1_TXD-Pad8)") (class "Default")
      (node (ref "U2") (pin "8") (pinfunction "JTAG_TDI_/_PULSE_CNTR1_/_UART1_TXD_8") (pintype "bidirectional"))
    )
    (net (code "79") (name "unconnected-(U2-JTAG_TDO_{slash}_PULSE_CNTR2_{slash}_UART1_RXD-Pad10)") (class "Default")
      (node (ref "U2") (pin "10") (pinfunction "JTAG_TDO_/_PULSE_CNTR2_/_UART1_RXD_10") (pintype "bidirectional"))
    )
    (net (code "80") (name "unconnected-(U2-M_CLK2_{slash}_UART3_DE-Pad26)") (class "Default")
      (node (ref "U2") (pin "26") (pinfunction "M_CLK2_/_UART3_DE_26") (pintype "bidirectional"))
    )
    (net (code "81") (name "unconnected-(U2-M_CLK3_{slash}_UART3_RE-Pad37)") (class "Default")
      (node (ref "U2") (pin "37") (pinfunction "M_CLK3_/_UART3_RE_37") (pintype "bidirectional"))
    )
    (net (code "82") (name "unconnected-(U2-OSPI_CLK_{slash}_QSPI0_CLK-Pad23)") (class "Default")
      (node (ref "U2") (pin "23") (pinfunction "OSPI_CLK_/_QSPI0_CLK_23") (pintype "bidirectional"))
    )
    (net (code "83") (name "unconnected-(U2-OSPI_CS_{slash}_QSPI0_CS0-Pad24)") (class "Default")
      (node (ref "U2") (pin "24") (pinfunction "OSPI_CS_/_QSPI0_CS0_24") (pintype "bidirectional"))
    )
    (net (code "84") (name "unconnected-(U2-OSPI_D0_{slash}_QSPI1_CS4_{slash}_QSPI0_D0-Pad19)") (class "Default")
      (node (ref "U2") (pin "19") (pinfunction "OSPI_D0_/_QSPI1_CS4_/_QSPI0_D0_19") (pintype "bidirectional"))
    )
    (net (code "85") (name "unconnected-(U2-OSPI_D1_{slash}_QSPI1_CS3_{slash}_QSPI0_D1-Pad21)") (class "Default")
      (node (ref "U2") (pin "21") (pinfunction "OSPI_D1_/_QSPI1_CS3_/_QSPI0_D1_21") (pintype "bidirectional"))
    )
    (net (code "86") (name "unconnected-(U2-OSPI_D2_{slash}_QSPI1_CS2_{slash}_QSPI0_D2-Pad36)") (class "Default")
      (node (ref "U2") (pin "36") (pinfunction "OSPI_D2_/_QSPI1_CS2_/_QSPI0_D2_36") (pintype "bidirectional"))
    )
    (net (code "87") (name "unconnected-(U2-OSPI_D3_{slash}_QSPI1_CS1_{slash}_QSPI0_D3-Pad11)") (class "Default")
      (node (ref "U2") (pin "11") (pinfunction "OSPI_D3_/_QSPI1_CS1_/_QSPI0_D3_11") (pintype "bidirectional"))
    )
    (net (code "88") (name "unconnected-(U2-OSPI_D4_{slash}_QSPI1_CS0_{slash}_PULSE_CNTR0-Pad12)") (class "Default")
      (node (ref "U2") (pin "12") (pinfunction "OSPI_D4_/_QSPI1_CS0_/_PULSE_CNTR0_12") (pintype "bidirectional"))
    )
    (net (code "89") (name "unconnected-(U2-OSPI_D5_{slash}_QSPI1_CLK_{slash}_PULSE_CNTR1-Pad40)") (class "Default")
      (node (ref "U2") (pin "40") (pinfunction "OSPI_D5_/_QSPI1_CLK_/_PULSE_CNTR1_40") (pintype "bidirectional"))
    )
    (net (code "90") (name "unconnected-(U2-OSPI_D6_{slash}_QSPI1_D0_{slash}_PULSE_CNTR2-Pad38)") (class "Default")
      (node (ref "U2") (pin "38") (pinfunction "OSPI_D6_/_QSPI1_D0_/_PULSE_CNTR2_38") (pintype "bidirectional"))
    )
    (net (code "91") (name "unconnected-(U2-OSPI_D7_{slash}_QSPI1_D1_{slash}_PULSE_CNTR3-Pad35)") (class "Default")
      (node (ref "U2") (pin "35") (pinfunction "OSPI_D7_/_QSPI1_D1_/_PULSE_CNTR3_35") (pintype "bidirectional"))
    )
    (net (code "92") (name "unconnected-(U2-OSPI_DQS_{slash}_QSPI1_D2_{slash}_PULSE_CNTR4-Pad31)") (class "Default")
      (node (ref "U2") (pin "31") (pinfunction "OSPI_DQS_/_QSPI1_D2_/_PULSE_CNTR4_31") (pintype "bidirectional"))
    )
    (net (code "93") (name "unconnected-(U2-PWM0_{slash}_IIC0_SCL_{slash}_QSPI0_CS2_{slash}_HSYNC1-Pad33)") (class "Default")
      (node (ref "U2") (pin "33") (pinfunction "PWM0_/_IIC0_SCL_/_QSPI0_CS2_/_HSYNC1_33") (pintype "bidirectional"))
    )
    (net (code "94") (name "unconnected-(U2-PWM1_{slash}_IIC0_SDA_{slash}_QSPI0_CS1_{slash}_VSYNC1-Pad32)") (class "Default")
      (node (ref "U2") (pin "32") (pinfunction "PWM1_/_IIC0_SDA_/_QSPI0_CS1_/_VSYNC1_32") (pintype "bidirectional"))
    )
    (net (code "95") (name "unconnected-(U2-PWM5_{slash}_QSPI1_D3_{slash}_PULSE_CNTR5-Pad29)") (class "Default")
      (node (ref "U2") (pin "29") (pinfunction "PWM5_/_QSPI1_D3_/_PULSE_CNTR5_29") (pintype "bidirectional"))
    )
    (net (code "96") (name "unconnected-(U3-3.3V-Pad15)") (class "Default")
      (node (ref "U3") (pin "15") (pinfunction "3.3V_15") (pintype "unspecified"))
    )
    (net (code "97") (name "unconnected-(U3-3.3V-Pad27)") (class "Default")
      (node (ref "U3") (pin "27") (pinfunction "3.3V_27") (pintype "unspecified"))
    )
    (net (code "98") (name "unconnected-(U3-3.3V-Pad52)") (class "Default")
      (node (ref "U3") (pin "52") (pinfunction "3.3V_52") (pintype "unspecified"))
    )
    (net (code "99") (name "unconnected-(U3-5-Pad7)") (class "Default")
      (node (ref "U3") (pin "7") (pinfunction "5_7") (pintype "unspecified"))
    )
    (net (code "100") (name "unconnected-(U3-6-Pad8)") (class "Default")
      (node (ref "U3") (pin "8") (pinfunction "6_8") (pintype "unspecified"))
    )
    (net (code "101") (name "unconnected-(U3-22-Pad29)") (class "Default")
      (node (ref "U3") (pin "29") (pinfunction "22_29") (pintype "unspecified"))
    )
    (net (code "102") (name "unconnected-(U3-23-Pad28)") (class "Default")
      (node (ref "U3") (pin "28") (pinfunction "23_28") (pintype "unspecified"))
    )
    (net (code "103") (name "unconnected-(U3-25_{slash}_RX6-Pad17)") (class "Default")
      (node (ref "U3") (pin "17") (pinfunction "25_/_RX6_17") (pintype "unspecified"))
    )
    (net (code "104") (name "unconnected-(U3-26-Pad18)") (class "Default")
      (node (ref "U3") (pin "18") (pinfunction "26_18") (pintype "unspecified"))
    )
    (net (code "105") (name "unconnected-(U3-27-Pad19)") (class "Default")
      (node (ref "U3") (pin "19") (pinfunction "27_19") (pintype "unspecified"))
    )
    (net (code "106") (name "unconnected-(U3-30-Pad22)") (class "Default")
      (node (ref "U3") (pin "22") (pinfunction "30_22") (pintype "unspecified"))
    )
    (net (code "107") (name "unconnected-(U3-31-Pad23)") (class "Default")
      (node (ref "U3") (pin "23") (pinfunction "31_23") (pintype "unspecified"))
    )
    (net (code "108") (name "unconnected-(U3-GND-Pad39)") (class "Default")
      (node (ref "U3") (pin "39") (pinfunction "GND_39") (pintype "unspecified"))
    )
    (net (code "109") (name "unconnected-(U3-LED_{slash}_13-Pad38)") (class "Default")
      (node (ref "U3") (pin "38") (pinfunction "LED_/_13_38") (pintype "unspecified"))
    )
    (net (code "110") (name "unconnected-(U3-On_{slash}_Off-Pad49)") (class "Default")
      (node (ref "U3") (pin "49") (pinfunction "On_/_Off_49") (pintype "unspecified"))
    )
    (net (code "111") (name "unconnected-(U3-RX3_{slash}_15-Pad36)") (class "Default")
      (node (ref "U3") (pin "36") (pinfunction "RX3_/_15_36") (pintype "unspecified"))
    )
    (net (code "112") (name "unconnected-(U3-RX5_{slash}_21-Pad30)") (class "Default")
      (node (ref "U3") (pin "30") (pinfunction "RX5_/_21_30") (pintype "unspecified"))
    )
    (net (code "113") (name "unconnected-(U3-TX8_{slash}_35-Pad46)") (class "Default")
      (node (ref "U3") (pin "46") (pinfunction "TX8_/_35_46") (pintype "unspecified"))
    )
    (net (code "114") (name "unconnected-(U3-VBat-Pad53)") (class "Default")
      (node (ref "U3") (pin "53") (pinfunction "VBat_53") (pintype "unspecified"))
    )
    (net (code "115") (name "unconnected-(U7-N{slash}C-Pad6)") (class "Default")
      (node (ref "U7") (pin "6") (pinfunction "N/C_6") (pintype "input"))
    )
  )
)
